# MSXIV_Discharge_Circuit.net
KiCad netlist of a schematic drawn in Altium Designer
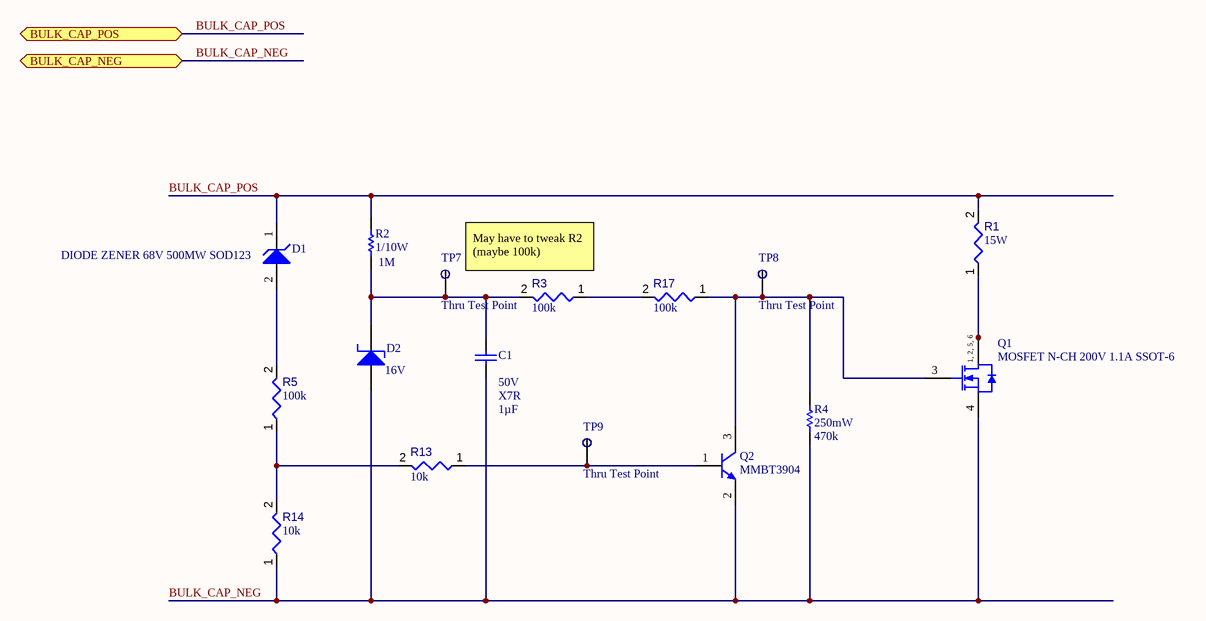
[diagram p0: MSXIV_Discharge_Circuit.SchDoc]

(export (version "E")
  (design (tool "Eeschema 10.0.6"))
  (components
    (comp (ref "C1")
      (value "1µF")
      (footprint "CAP, 0603")
      (description "1µF ±10% 50V Ceramic Capacitor X7R 0603 (1608 Metric)")
      (fields
        (field (name "VOLTAGE") "50V")
        (field (name "TEMPERATURE COEFFICIENT") "X7R")
        (field (name "TOLERANCE") "10%")
        (field (name "Comment") "CAP CER 1UF 50V 10% X7R 0603")
        (field (name "SOURCE") "Schematic Diagrams.SchLib")
      )
      (libsource (lib "University of Waterloo - Solar Car Team") (part "Symbol"))
    )
    (comp (ref "D1")
      (value "DIODE ZENER 68V 500MW SOD123")
      (footprint "ONSC-SOD-123-2-425-04_V")
      (description "Diode Zener Single 68V 5% 500mW Automotive 2-Pin SOD-123 T/R")
      (fields (field (name "TOLERANCE") "5%"))
      (libsource (lib "University of Waterloo - Solar Car Team") (part "ONSC-K1A2-2"))
    )
    (comp (ref "D2")
      (value "DIODE ZENER 16V 5W DO-214AA (SMB)_1")
      (footprint "DO-214AA Diode")
      (description "Zener Diode 16V 5W ±5% Surface Mount DO-214AA (SMB)")
      (fields
        (field (name "VOLTAGE - ZENER (NOM)") "16V")
        (field (name "MANUFACTURE PART NUMBER") "SMBJ5353B-TP")
        (field (name "SOURCE") "Schematic Diagrams.SchLib")
      )
      (libsource (lib "") (part "Symbol_2"))
    )
    (comp (ref "Q1")
      (value "MOSFET N-CH 200V 1.1A SSOT-6")
      (footprint "FAIR-SOT23-6_V")
      (description "Trans MOSFET N-CH 200V 1.1A 6-Pin SuperSOT T/R")
      (libsource (lib "University of Waterloo - Solar Car Team") (part "NEMOS-DDGSDD-6"))
    )
    (comp (ref "Q2")
      (value "MMBT3904")
      (footprint "FAIR-SOT23-3_V")
      (description "NPN General Purpose Amplifier, 40 V, 0.2 A, -55 to 150 degC, 3-Pin SOT23, RoHS, Tape and Reel")
      (fields (field (name "MANUFACTURER") "Fairchild Semiconductor") (field (name "POWER") "625mW"))
      (libsource (lib "University of Waterloo - Solar Car Team") (part "BJT-NPN-BEC-3"))
    )
    (comp (ref "R1")
      (value "RES 1K OHM 15W 1% TO126")
      (footprint "MP915-1.00K-1%-Footprint-1")
      (description "1 kOhms ±1% 15W Through Hole Resistor TO-126-2 Moisture Resistant, Non-Inductive Thick Film")
      (fields (field (name "TOLERANCE") "1%") (field (name "MAX POWER DISSIPATION") "15W"))
      (libsource (lib "University of Waterloo - Solar Car Team") (part "RES-2"))
    )
    (comp (ref "R2")
      (value "RES 1M OHM 1% 1/10W 0603")
      (footprint "RES, 0603")
      (description "1M Ohm ±1% 0.1W, 1/10W Chip Resistor 0603 (1608 Metric) Moisture Resistant Thick Film")
      (fields
        (field (name "POWER (WATTS)") "1/10W")
        (field (name "RESISTANCE (OHMS)") "1M")
        (field (name "TOLERANCE") "1%")
        (field (name "SOURCE") "Schematic Diagrams.SchLib")
      )
      (libsource (lib "") (part "Symbol_1"))
    )
    (comp (ref "R3")
      (value "100k")
      (footprint "RESC2013X70X40ML20T20")
      (description "Chip Resistor, 100 KOhm, +/- 1%, 0.125 W, -55 to 155 degC, 0805 (2012 Metric)")
      (fields (field (name "POWER") "125mW") (field (name "TOLERANCE") "1%"))
      (libsource (lib "University of Waterloo - Solar Car Team") (part "RES-2"))
    )
    (comp (ref "R4")
      (value "470k")
      (footprint "RES 1206")
      (fields
        (field (name "MAX POWER DISSIPATION") "250mW")
        (field (name "TOLERANCE") "0.1%")
        (field (name "MANUFACTURER PART NUMBER") "RG3216P-4703-B-T1")
        (field (name "MANUFACTURER") "Susumu")
        (field (name "SOURCE") "Schematic Diagrams.SchLib")
      )
      (libsource (lib "") (part "Symbol_1"))
    )
    (comp (ref "R5")
      (value "100k")
      (footprint "RESC2013X70X40ML20T20")
      (description "Chip Resistor, 100 KOhm, +/- 1%, 0.125 W, -55 to 155 degC, 0805 (2012 Metric)")
      (fields (field (name "POWER") "125mW") (field (name "TOLERANCE") "1%"))
      (libsource (lib "University of Waterloo - Solar Car Team") (part "RES-2"))
    )
    (comp (ref "R13")
      (value "10k")
      (footprint "RESC2013X50X35ML15T15")
      (description "Chip Resistor, 10 KOhm, +/- 1%, 125 mW, -55 to 155 degC, 0805 (2012 Metric)")
      (fields (field (name "POWER") "125mW") (field (name "TOLERANCE") "1%"))
      (libsource (lib "University of Waterloo - Solar Car Team") (part "RES-2"))
    )
    (comp (ref "R14")
      (value "10k")
      (footprint "RESC2013X50X35ML15T15")
      (description "Chip Resistor, 10 KOhm, +/- 1%, 125 mW, -55 to 155 degC, 0805 (2012 Metric)")
      (fields (field (name "POWER") "125mW") (field (name "TOLERANCE") "1%"))
      (libsource (lib "University of Waterloo - Solar Car Team") (part "RES-2"))
    )
    (comp (ref "R17")
      (value "100k")
      (footprint "RESC2013X70X40ML20T20")
      (description "Chip Resistor, 100 KOhm, +/- 1%, 0.125 W, -55 to 155 degC, 0805 (2012 Metric)")
      (fields (field (name "POWER") "125mW") (field (name "TOLERANCE") "1%"))
      (libsource (lib "University of Waterloo - Solar Car Team") (part "RES-2"))
    )
    (comp (ref "TP7")
      (value "Thru Test Point")
      (footprint "Thru Test Point")
      (fields (field (name "SOURCE") "Schematic Diagrams.SchLib"))
      (libsource (lib "University of Waterloo - Solar Car Team") (part "Thru Test Point"))
    )
    (comp (ref "TP8")
      (value "Thru Test Point")
      (footprint "Thru Test Point")
      (fields (field (name "SOURCE") "Schematic Diagrams.SchLib"))
      (libsource (lib "University of Waterloo - Solar Car Team") (part "Thru Test Point"))
    )
    (comp (ref "TP9")
      (value "Thru Test Point")
      (footprint "Thru Test Point")
      (fields (field (name "SOURCE") "Schematic Diagrams.SchLib"))
      (libsource (lib "University of Waterloo - Solar Car Team") (part "Thru Test Point"))
    )
  )
  (nets
    (net (code "1") (name "/BULK_CAP_NEG") (class "Default")
      (node (ref "C1") (pin "2") (pinfunction "2_2") (pintype "passive"))
      (node (ref "D2") (pin "1") (pinfunction "A_1") (pintype "passive"))
      (node (ref "Q1") (pin "4") (pinfunction "S_4") (pintype "passive"))
      (node (ref "Q2") (pin "2") (pinfunction "E_2") (pintype "passive"))
      (node (ref "R14") (pin "1") (pinfunction "1_1") (pintype "passive"))
      (node (ref "R4") (pin "2") (pinfunction "2_2") (pintype "passive"))
    )
    (net (code "2") (name "/BULK_CAP_POS") (class "Default")
      (node (ref "D1") (pin "1") (pinfunction "K_1") (pintype "passive"))
      (node (ref "R1") (pin "2") (pinfunction "2_2") (pintype "passive"))
      (node (ref "R2") (pin "1") (pinfunction "1_1") (pintype "passive"))
    )
    (net (code "3") (name "Net-(D1-A)") (class "Default")
      (node (ref "D1") (pin "2") (pinfunction "A_2") (pintype "passive"))
      (node (ref "R5") (pin "2") (pinfunction "2_2") (pintype "passive"))
    )
    (net (code "4") (name "Net-(D2-K)") (class "Default")
      (node (ref "C1") (pin "1") (pinfunction "1_1") (pintype "passive"))
      (node (ref "D2") (pin "2") (pinfunction "K_2") (pintype "passive"))
      (node (ref "R2") (pin "2") (pinfunction "2_2") (pintype "passive"))
      (node (ref "R3") (pin "2") (pinfunction "2_2") (pintype "passive"))
      (node (ref "TP7") (pin "TH_TP") (pinfunction "1_TH_TP") (pintype "passive"))
    )
    (net (code "5") (name "Net-(Q1-D-Pad1)") (class "Default")
      (node (ref "Q1") (pin "1") (pinfunction "D_1") (pintype "passive"))
      (node (ref "Q1") (pin "2") (pinfunction "D_2") (pintype "passive"))
      (node (ref "Q1") (pin "5") (pinfunction "D_5") (pintype "passive"))
      (node (ref "Q1") (pin "6") (pinfunction "D_6") (pintype "passive"))
      (node (ref "R1") (pin "1") (pinfunction "1_1") (pintype "passive"))
    )
    (net (code "6") (name "Net-(Q1-G)") (class "Default")
      (node (ref "Q1") (pin "3") (pinfunction "G_3") (pintype "passive"))
      (node (ref "Q2") (pin "3") (pinfunction "C_3") (pintype "passive"))
      (node (ref "R17") (pin "1") (pinfunction "1_1") (pintype "passive"))
      (node (ref "R4") (pin "1") (pinfunction "1_1") (pintype "passive"))
      (node (ref "TP8") (pin "TH_TP") (pinfunction "1_TH_TP") (pintype "passive"))
    )
    (net (code "7") (name "Net-(Q2-B)") (class "Default")
      (node (ref "Q2") (pin "1") (pinfunction "B_1") (pintype "passive"))
      (node (ref "R13") (pin "1") (pinfunction "1_1") (pintype "passive"))
      (node (ref "TP9") (pin "TH_TP") (pinfunction "1_TH_TP") (pintype "passive"))
    )
    (net (code "8") (name "Net-(R13-Pad2)") (class "Default")
      (node (ref "R13") (pin "2") (pinfunction "2_2") (pintype "passive"))
      (node (ref "R14") (pin "2") (pinfunction "2_2") (pintype "passive"))
      (node (ref "R5") (pin "1") (pinfunction "1_1") (pintype "passive"))
    )
    (net (code "9") (name "Net-(R17-Pad2)") (class "Default")
      (node (ref "R17") (pin "2") (pinfunction "2_2") (pintype "passive"))
      (node (ref "R3") (pin "1") (pinfunction "1_1") (pintype "passive"))
    )
  )
)
